# mcu.net
KiCad netlist of a schematic drawn in Altium Designer
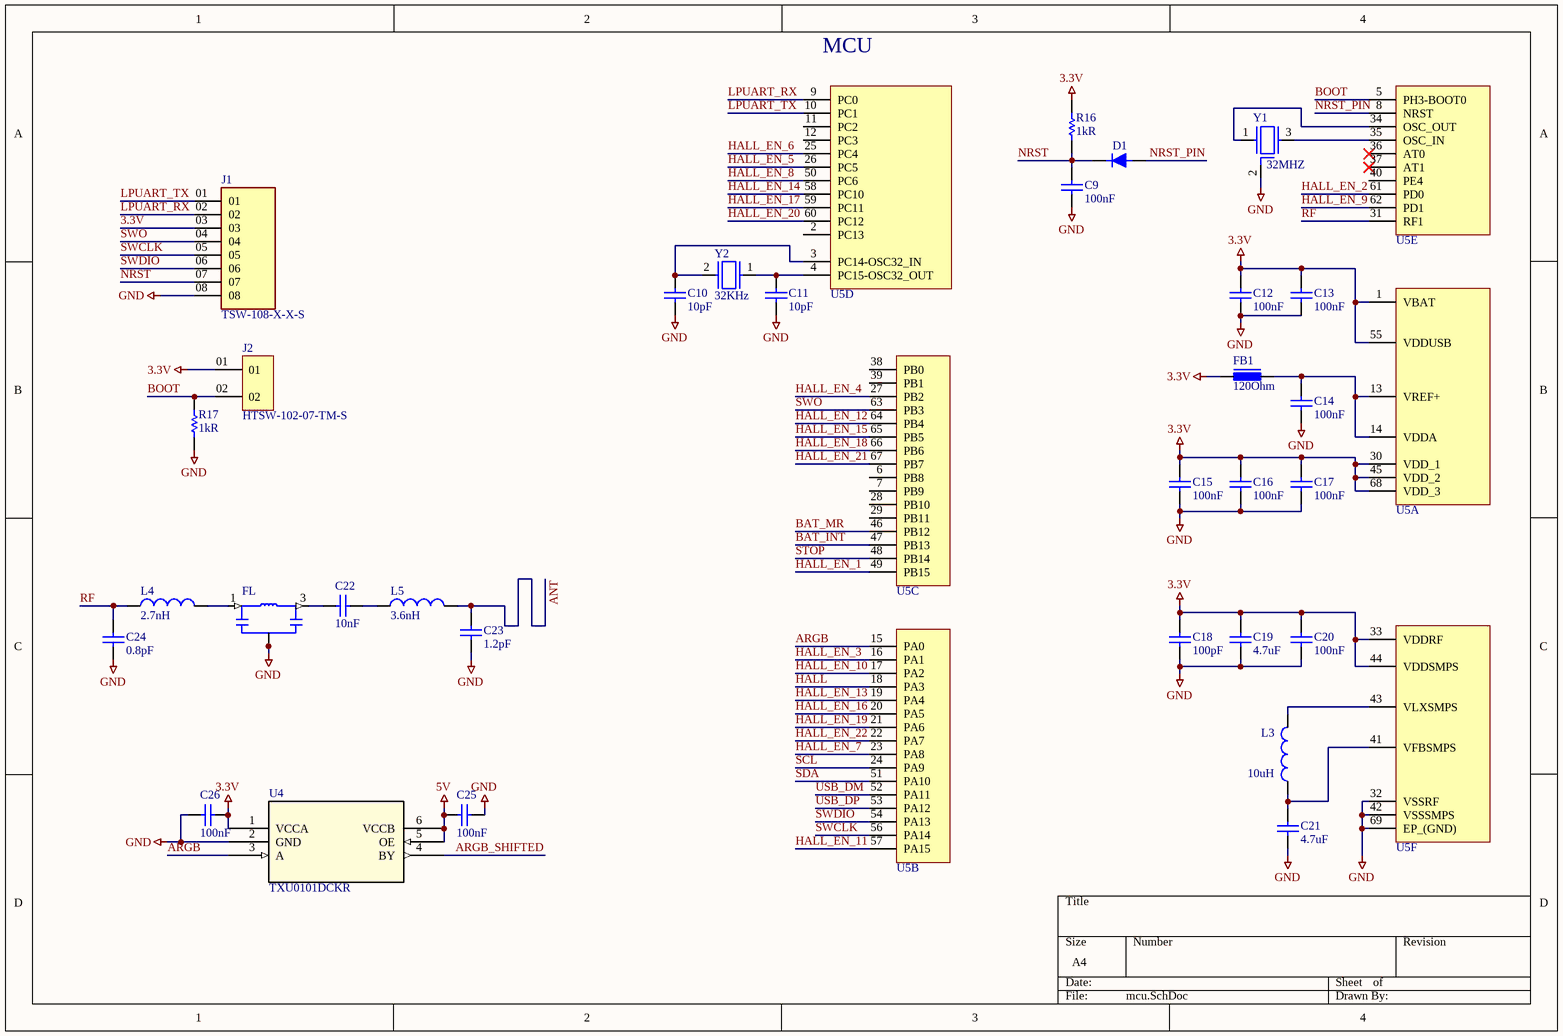
[diagram p0: mcu.SchDoc]

(export (version "E")
  (design (tool "Eeschema 10.0.6"))
  (components
    (comp (ref "C9")
      (value "100nF")
      (footprint "CAP_0402")
      (fields (field (name "MF") "Murata") (field (name "MP") "GRM022R60J222KE19L"))
      (libsource (lib "CAP_SMD") (part "Cap_100nF_0402"))
    )
    (comp (ref "C10")
      (value "10pF")
      (footprint "CAP_0402")
      (fields (field (name "MF") "Murata") (field (name "MP") "GRM022R60J222KE19L"))
      (libsource (lib "CAP_SMD") (part "Cap_10pF_0402"))
    )
    (comp (ref "C11")
      (value "10pF")
      (footprint "CAP_0402")
      (fields (field (name "MF") "Murata") (field (name "MP") "GRM022R60J222KE19L"))
      (libsource (lib "CAP_SMD") (part "Cap_10pF_0402"))
    )
    (comp (ref "C12")
      (value "100nF")
      (footprint "CAP_0402")
      (fields (field (name "MF") "Murata") (field (name "MP") "GRM022R60J222KE19L"))
      (libsource (lib "CAP_SMD") (part "Cap_100nF_0402"))
    )
    (comp (ref "C13")
      (value "100nF")
      (footprint "CAP_0402")
      (fields (field (name "MF") "Murata") (field (name "MP") "GRM022R60J222KE19L"))
      (libsource (lib "CAP_SMD") (part "Cap_100nF_0402"))
    )
    (comp (ref "C14")
      (value "100nF")
      (footprint "CAP_0402")
      (fields (field (name "MF") "Murata") (field (name "MP") "GRM022R60J222KE19L"))
      (libsource (lib "CAP_SMD") (part "Cap_100nF_0402"))
    )
    (comp (ref "C15")
      (value "100nF")
      (footprint "CAP_0402")
      (fields (field (name "MF") "Murata") (field (name "MP") "GRM022R60J222KE19L"))
      (libsource (lib "CAP_SMD") (part "Cap_100nF_0402"))
    )
    (comp (ref "C16")
      (value "100nF")
      (footprint "CAP_0402")
      (fields (field (name "MF") "Murata") (field (name "MP") "GRM022R60J222KE19L"))
      (libsource (lib "CAP_SMD") (part "Cap_100nF_0402"))
    )
    (comp (ref "C17")
      (value "100nF")
      (footprint "CAP_0402")
      (fields (field (name "MF") "Murata") (field (name "MP") "GRM022R60J222KE19L"))
      (libsource (lib "CAP_SMD") (part "Cap_100nF_0402"))
    )
    (comp (ref "C18")
      (value "100pF")
      (footprint "CAP_0402")
      (fields (field (name "MF") "Murata") (field (name "MP") "GRM022R60J222KE19L"))
      (libsource (lib "CAP_SMD") (part "Cap_100pF_0402"))
    )
    (comp (ref "C19")
      (value "4.7uF")
      (footprint "CAP_0402")
      (fields (field (name "MF") "Murata") (field (name "MP") "GRM022R60J222KE19L"))
      (libsource (lib "CAP_SMD") (part "Cap_4.7uF_0402"))
    )
    (comp (ref "C20")
      (value "100nF")
      (footprint "CAP_0402")
      (fields (field (name "MF") "Murata") (field (name "MP") "GRM022R60J222KE19L"))
      (libsource (lib "CAP_SMD") (part "Cap_100nF_0402"))
    )
    (comp (ref "C21")
      (value "4.7uF")
      (footprint "CAP_0402")
      (fields (field (name "MF") "Murata") (field (name "MP") "GRM022R60J222KE19L"))
      (libsource (lib "CAP_SMD") (part "Cap_4.7uF_0402"))
    )
    (comp (ref "C22")
      (value "10nF")
      (footprint "CAP_0402")
      (fields (field (name "MF") "Murata") (field (name "MP") "GRM022R60J222KE19L"))
      (libsource (lib "CAP_SMD") (part "Cap_10nF_0402"))
    )
    (comp (ref "C23")
      (value "1.2pF")
      (footprint "CAP_0402")
      (fields (field (name "MF") "Murata") (field (name "MP") "GRM022R60J222KE19L"))
      (libsource (lib "CAP_SMD") (part "Cap_1.2pF_0402"))
    )
    (comp (ref "C24")
      (value "0.8pF")
      (footprint "CAP_0402")
      (fields (field (name "MF") "Murata") (field (name "MP") "GRM022R60J222KE19L"))
      (libsource (lib "CAP_SMD") (part "Cap_0.8pF_0402"))
    )
    (comp (ref "C25")
      (value "100nF")
      (footprint "CAP_0402")
      (fields (field (name "MF") "Murata") (field (name "MP") "GRM022R60J222KE19L"))
      (libsource (lib "CAP_SMD") (part "Cap_100nF_0402"))
    )
    (comp (ref "C26")
      (value "100nF")
      (footprint "CAP_0402")
      (fields (field (name "MF") "Murata") (field (name "MP") "GRM022R60J222KE19L"))
      (libsource (lib "CAP_SMD") (part "Cap_100nF_0402"))
    )
    (comp (ref "D1")
      (value "0.3A")
      (footprint "SODFL1608X70N")
      (description "BAT54KFILM, Schottky Diode,  0.3A max, 40V 5ns, 2-Pin, SOD-523")
      (fields
        (field (name "MOUSER PART NUMBER") "511-BAT54KFILM")
        (field (name "MANUFACTURER_PART_NUMBER") "BAT54KFILM")
      )
      (libsource (lib "CHOCO_KEYBOARD") (part "BAT54KFILM"))
    )
    (comp (ref "FB1")
      (value "120Ohm")
      (footprint "BEADC1005X50N")
      (description "Ferrite Bead")
      (fields (field (name "MF") "Tai Tech") (field (name "MP") "FCM1608KF-601T05"))
      (libsource (lib "CHOCO_KEYBOARD") (part "MMZ1005S121CTD25"))
    )
    (comp (ref "FL")
      (value "LFB182G45CGFD436")
      (footprint "FIL_LFB182G45CGFD436")
      (description "RF Filter Band Pass 2450MHz 2400MHz to 2500MHz 2.8dB 50Ohm SMD 6Pin 0603")
      (fields (field (name "MF") "Murata"))
      (libsource (lib "LFB182G45CGFD436") (part "LFB182G45CGFD436"))
    )
    (comp (ref "J1")
      (value "TSW-108-X-X-S")
      (footprint "SAMTEC_TSW-108-X-X-S")
      (description "Connector Header Through Hole 8 position 0.100 (2.54mm)")
      (fields (field (name "MF") "Samtec") (field (name "MP") "TSW-108-23-L-S"))
      (libsource (lib "TSW-108-X-X-S") (part "TSW-108-X-X-S"))
    )
    (comp (ref "J2")
      (value "HTSW-102-07-TM-S")
      (footprint "SAMTEC_HTSW-102-07-TM-S")
      (fields (field (name "MP") "HTSW10207TMS") (field (name "MF") "Samtec"))
      (libsource (lib "CHOCO_KEYBOARD") (part "HTSW-102-07-TM-S"))
    )
    (comp (ref "L3")
      (value "10uH")
      (footprint "INDC1106X70N")
      (description "Inductor with Inductance: 10uH Tol. +/-20%, Package: 0402 (1005)")
      (fields (field (name "MP") "LQW15DN100M00D") (field (name "MF") "Murata Electronics North America"))
      (libsource (lib "LQW15DN100M00D") (part "LQW15DN100M00D"))
    )
    (comp (ref "L4")
      (value "2.7nH")
      (footprint "INDC1005X55N")
      (description "Inductor with Inductance: 3.6nH Tol. +/-0.3nH, Package: 0402 _1005_")
      (fields (field (name "MP") "LQG15HS3N6S02D") (field (name "MF") "Murata"))
      (libsource (lib "LQG15HS3N6S02D") (part "LQG15HS3N6S02D"))
    )
    (comp (ref "L5")
      (value "3.6nH")
      (footprint "INDC1005X55N")
      (description "Inductor with Inductance: 3.6nH Tol. +/-0.3nH, Package: 0402 _1005_")
      (fields (field (name "MP") "LQG15HS3N6S02D") (field (name "MF") "Murata"))
      (libsource (lib "LQG15HS3N6S02D") (part "LQG15HS3N6S02D"))
    )
    (comp (ref "R16") (value "1kR") (footprint "RES_0402") (libsource (lib "RES_SMD") (part "Res_1kR_0402")))
    (comp (ref "R17") (value "1kR") (footprint "RES_0402") (libsource (lib "RES_SMD") (part "Res_1kR_0402")))
    (comp (ref "U4")
      (value "TXU0101DCKR")
      (footprint "TXU0101DCKR")
      (libsource (lib "CHOCO_KEYBOARD") (part "TXU0101DCKR"))
    )
    (comp (ref "U5")
      (value "STM32WB55RGV6")
      (footprint "QFN40P800X800X100-69L-D")
      (libsource (lib "CHOCO_KEYBOARD") (part "STM32WB55RGV6"))
    )
    (comp (ref "Y1")
      (value "32MHZ")
      (footprint "SamacSys:NX2016SA32MEXS00ACS06465")
      (description "Crystal or Oscillator")
      (fields
        (field (name "MANUFACTURER_PART_NUMBER") "NX2016SA-26MHZ-EXS00A-CS06025")
        (field (name "MOUSER PART NUMBER") "344-NX2016SA26S06025")
      )
      (libsource (lib "CHOCO_KEYBOARD") (part "NX2016SA-32MHZ"))
    )
    (comp (ref "Y2")
      (value "32KHz")
      (footprint "SamacSys:NX2012SA32768KSTDMUB1")
      (description "Crystal or Oscillator")
      (fields
        (field (name "MANUFACTURER_PART_NUMBER") "NX2012SA-32.768K-STD-MUB-1")
        (field (name "MOUSER PART NUMBER") "344-NX2012SA32768K1")
      )
      (libsource (lib "CHOCO_KEYBOARD") (part "NX2012SA-32.768K"))
    )
  )
  (nets
    (net (code "1") (name "/ANT") (class "Default")
      (node (ref "C23") (pin "1") (pinfunction "1_1") (pintype "passive"))
      (node (ref "L5") (pin "2") (pinfunction "2_2") (pintype "passive"))
    )
    (net (code "2") (name "/ARGB") (class "Default")
      (node (ref "U4") (pin "3") (pinfunction "A_3") (pintype "input"))
      (node (ref "U5") (pin "15") (pinfunction "PA0_15") (pintype "passive"))
    )
    (net (code "3") (name "/ARGB_SHIFTED") (class "Default")
      (node (ref "U4") (pin "4") (pinfunction "BY_4") (pintype "output"))
    )
    (net (code "4") (name "/BAT_INT") (class "Default")
      (node (ref "U5") (pin "47") (pinfunction "PB13_47") (pintype "passive"))
    )
    (net (code "5") (name "/BAT_MR") (class "Default")
      (node (ref "U5") (pin "46") (pinfunction "PB12_46") (pintype "passive"))
    )
    (net (code "6") (name "/BOOT") (class "Default")
      (node (ref "J2") (pin "02") (pinfunction "02_02") (pintype "passive"))
      (node (ref "R17") (pin "2") (pinfunction "2_2") (pintype "passive"))
      (node (ref "U5") (pin "5") (pinfunction "PH3-BOOT0_5") (pintype "passive"))
    )
    (net (code "7") (name "/HALL") (class "Default")
      (node (ref "U5") (pin "18") (pinfunction "PA3_18") (pintype "passive"))
    )
    (net (code "8") (name "/HALL_EN_1") (class "Default")
      (node (ref "U5") (pin "49") (pinfunction "PB15_49") (pintype "passive"))
    )
    (net (code "9") (name "/HALL_EN_2") (class "Default")
      (node (ref "U5") (pin "61") (pinfunction "PD0_61") (pintype "passive"))
    )
    (net (code "10") (name "/HALL_EN_3") (class "Default")
      (node (ref "U5") (pin "16") (pinfunction "PA1_16") (pintype "passive"))
    )
    (net (code "11") (name "/HALL_EN_4") (class "Default")
      (node (ref "U5") (pin "27") (pinfunction "PB2_27") (pintype "passive"))
    )
    (net (code "12") (name "/HALL_EN_5") (class "Default")
      (node (ref "U5") (pin "26") (pinfunction "PC5_26") (pintype "passive"))
    )
    (net (code "13") (name "/HALL_EN_6") (class "Default")
      (node (ref "U5") (pin "25") (pinfunction "PC4_25") (pintype "passive"))
    )
    (net (code "14") (name "/HALL_EN_7") (class "Default")
      (node (ref "U5") (pin "23") (pinfunction "PA8_23") (pintype "passive"))
    )
    (net (code "15") (name "/HALL_EN_8") (class "Default")
      (node (ref "U5") (pin "50") (pinfunction "PC6_50") (pintype "passive"))
    )
    (net (code "16") (name "/HALL_EN_9") (class "Default")
      (node (ref "U5") (pin "62") (pinfunction "PD1_62") (pintype "passive"))
    )
    (net (code "17") (name "/HALL_EN_10") (class "Default")
      (node (ref "U5") (pin "17") (pinfunction "PA2_17") (pintype "passive"))
    )
    (net (code "18") (name "/HALL_EN_11") (class "Default")
      (node (ref "U5") (pin "57") (pinfunction "PA15_57") (pintype "passive"))
    )
    (net (code "19") (name "/HALL_EN_12") (class "Default")
      (node (ref "U5") (pin "64") (pinfunction "PB4_64") (pintype "passive"))
    )
    (net (code "20") (name "/HALL_EN_13") (class "Default")
      (node (ref "U5") (pin "19") (pinfunction "PA4_19") (pintype "passive"))
    )
    (net (code "21") (name "/HALL_EN_14") (class "Default")
      (node (ref "U5") (pin "58") (pinfunction "PC10_58") (pintype "passive"))
    )
    (net (code "22") (name "/HALL_EN_15") (class "Default")
      (node (ref "U5") (pin "65") (pinfunction "PB5_65") (pintype "passive"))
    )
    (net (code "23") (name "/HALL_EN_16") (class "Default")
      (node (ref "U5") (pin "20") (pinfunction "PA5_20") (pintype "passive"))
    )
    (net (code "24") (name "/HALL_EN_17") (class "Default")
      (node (ref "U5") (pin "59") (pinfunction "PC11_59") (pintype "passive"))
    )
    (net (code "25") (name "/HALL_EN_18") (class "Default")
      (node (ref "U5") (pin "66") (pinfunction "PB6_66") (pintype "passive"))
    )
    (net (code "26") (name "/HALL_EN_19") (class "Default")
      (node (ref "U5") (pin "21") (pinfunction "PA6_21") (pintype "passive"))
    )
    (net (code "27") (name "/HALL_EN_20") (class "Default")
      (node (ref "U5") (pin "60") (pinfunction "PC12_60") (pintype "passive"))
    )
    (net (code "28") (name "/HALL_EN_21") (class "Default")
      (node (ref "U5") (pin "67") (pinfunction "PB7_67") (pintype "passive"))
    )
    (net (code "29") (name "/HALL_EN_22") (class "Default")
      (node (ref "U5") (pin "22") (pinfunction "PA7_22") (pintype "passive"))
    )
    (net (code "30") (name "/LPUART_RX") (class "Default")
      (node (ref "J1") (pin "02") (pinfunction "02_02") (pintype "passive"))
      (node (ref "U5") (pin "9") (pinfunction "PC0_9") (pintype "passive"))
    )
    (net (code "31") (name "/LPUART_TX") (class "Default")
      (node (ref "J1") (pin "01") (pinfunction "01_01") (pintype "passive"))
      (node (ref "U5") (pin "10") (pinfunction "PC1_10") (pintype "passive"))
    )
    (net (code "32") (name "/NRST") (class "Default")
      (node (ref "C9") (pin "1") (pinfunction "1_1") (pintype "passive"))
      (node (ref "D1") (pin "1") (pinfunction "K_1") (pintype "passive"))
      (node (ref "J1") (pin "07") (pinfunction "07_07") (pintype "passive"))
      (node (ref "R16") (pin "1") (pinfunction "1_1") (pintype "passive"))
    )
    (net (code "33") (name "/NRST_PIN") (class "Default")
      (node (ref "D1") (pin "2") (pinfunction "A_2") (pintype "passive"))
      (node (ref "U5") (pin "8") (pinfunction "NRST_8") (pintype "passive"))
    )
    (net (code "34") (name "/RF") (class "Default")
      (node (ref "C24") (pin "2") (pinfunction "2_2") (pintype "passive"))
      (node (ref "L4") (pin "1") (pinfunction "1_1") (pintype "passive"))
      (node (ref "U5") (pin "31") (pinfunction "RF1_31") (pintype "passive"))
    )
    (net (code "35") (name "/SCL") (class "Default")
      (node (ref "U5") (pin "24") (pinfunction "PA9_24") (pintype "passive"))
    )
    (net (code "36") (name "/SDA") (class "Default")
      (node (ref "U5") (pin "51") (pinfunction "PA10_51") (pintype "passive"))
    )
    (net (code "37") (name "/STOP") (class "Default")
      (node (ref "U5") (pin "48") (pinfunction "PB14_48") (pintype "passive"))
    )
    (net (code "38") (name "/SWCLK") (class "Default")
      (node (ref "J1") (pin "05") (pinfunction "05_05") (pintype "passive"))
      (node (ref "U5") (pin "56") (pinfunction "PA14_56") (pintype "passive"))
    )
    (net (code "39") (name "/SWDIO") (class "Default")
      (node (ref "J1") (pin "06") (pinfunction "06_06") (pintype "passive"))
      (node (ref "U5") (pin "54") (pinfunction "PA13_54") (pintype "passive"))
    )
    (net (code "40") (name "/SWO") (class "Default")
      (node (ref "J1") (pin "04") (pinfunction "04_04") (pintype "passive"))
      (node (ref "U5") (pin "63") (pinfunction "PB3_63") (pintype "passive"))
    )
    (net (code "41") (name "/USB_DM") (class "Default")
      (node (ref "U5") (pin "52") (pinfunction "PA11_52") (pintype "passive"))
    )
    (net (code "42") (name "/USB_DP") (class "Default")
      (node (ref "U5") (pin "53") (pinfunction "PA12_53") (pintype "passive"))
    )
    (net (code "43") (name "3.3V") (class "Default")
      (node (ref "C12") (pin "2") (pinfunction "2_2") (pintype "passive"))
      (node (ref "C13") (pin "2") (pinfunction "2_2") (pintype "passive"))
      (node (ref "C15") (pin "2") (pinfunction "2_2") (pintype "passive"))
      (node (ref "C16") (pin "2") (pinfunction "2_2") (pintype "passive"))
      (node (ref "C17") (pin "2") (pinfunction "2_2") (pintype "passive"))
      (node (ref "C18") (pin "2") (pinfunction "2_2") (pintype "passive"))
      (node (ref "C19") (pin "2") (pinfunction "2_2") (pintype "passive"))
      (node (ref "C20") (pin "2") (pinfunction "2_2") (pintype "passive"))
      (node (ref "C26") (pin "1") (pinfunction "1_1") (pintype "passive"))
      (node (ref "FB1") (pin "1") (pinfunction "1_1") (pintype "passive"))
      (node (ref "J1") (pin "03") (pinfunction "03_03") (pintype "passive"))
      (node (ref "J2") (pin "01") (pinfunction "01_01") (pintype "passive"))
      (node (ref "R16") (pin "2") (pinfunction "2_2") (pintype "passive"))
      (node (ref "U4") (pin "1") (pinfunction "VCCA_1") (pintype "power_in"))
      (node (ref "U5") (pin "1") (pinfunction "VBAT_1") (pintype "passive"))
      (node (ref "U5") (pin "30") (pinfunction "VDD_1_30") (pintype "passive"))
      (node (ref "U5") (pin "33") (pinfunction "VDDRF_33") (pintype "passive"))
      (node (ref "U5") (pin "44") (pinfunction "VDDSMPS_44") (pintype "passive"))
      (node (ref "U5") (pin "45") (pinfunction "VDD_2_45") (pintype "passive"))
      (node (ref "U5") (pin "55") (pinfunction "VDDUSB_55") (pintype "passive"))
      (node (ref "U5") (pin "68") (pinfunction "VDD_3_68") (pintype "passive"))
    )
    (net (code "44") (name "5V") (class "Default")
      (node (ref "C25") (pin "2") (pinfunction "2_2") (pintype "passive"))
      (node (ref "U4") (pin "5") (pinfunction "OE_5") (pintype "input"))
      (node (ref "U4") (pin "6") (pinfunction "VCCB_6") (pintype "power_in"))
    )
    (net (code "45") (name "GND") (class "Default")
      (node (ref "C10") (pin "1") (pinfunction "1_1") (pintype "passive"))
      (node (ref "C11") (pin "1") (pinfunction "1_1") (pintype "passive"))
      (node (ref "C12") (pin "1") (pinfunction "1_1") (pintype "passive"))
      (node (ref "C13") (pin "1") (pinfunction "1_1") (pintype "passive"))
      (node (ref "C14") (pin "1") (pinfunction "1_1") (pintype "passive"))
      (node (ref "C15") (pin "1") (pinfunction "1_1") (pintype "passive"))
      (node (ref "C16") (pin "1") (pinfunction "1_1") (pintype "passive"))
      (node (ref "C17") (pin "1") (pinfunction "1_1") (pintype "passive"))
      (node (ref "C18") (pin "1") (pinfunction "1_1") (pintype "passive"))
      (node (ref "C19") (pin "1") (pinfunction "1_1") (pintype "passive"))
      (node (ref "C20") (pin "1") (pinfunction "1_1") (pintype "passive"))
      (node (ref "C21") (pin "1") (pinfunction "1_1") (pintype "passive"))
      (node (ref "C23") (pin "2") (pinfunction "2_2") (pintype "passive"))
      (node (ref "C24") (pin "1") (pinfunction "1_1") (pintype "passive"))
      (node (ref "C25") (pin "1") (pinfunction "1_1") (pintype "passive"))
      (node (ref "C26") (pin "2") (pinfunction "2_2") (pintype "passive"))
      (node (ref "C9") (pin "2") (pinfunction "2_2") (pintype "passive"))
      (node (ref "FL") (pin "2") (pinfunction "GND_2") (pintype "power_in"))
      (node (ref "FL") (pin "2_1") (pinfunction "GND_2_1") (pintype "power_in"))
      (node (ref "J1") (pin "08") (pinfunction "08_08") (pintype "passive"))
      (node (ref "R17") (pin "1") (pinfunction "1_1") (pintype "passive"))
      (node (ref "U4") (pin "2") (pinfunction "GND_2") (pintype "power_in"))
      (node (ref "U5") (pin "32") (pinfunction "VSSRF_32") (pintype "passive"))
      (node (ref "U5") (pin "42") (pinfunction "VSSSMPS_42") (pintype "passive"))
      (node (ref "U5") (pin "69") (pinfunction "EP_(GND)_69") (pintype "passive"))
      (node (ref "Y1") (pin "2") (pinfunction "GND_2") (pintype "passive"))
    )
    (net (code "46") (name "Net-(C22-Pad2)") (class "Default")
      (node (ref "C22") (pin "2") (pinfunction "2_2") (pintype "passive"))
      (node (ref "L5") (pin "1") (pinfunction "1_1") (pintype "passive"))
    )
    (net (code "47") (name "Net-(FL-IN)") (class "Default")
      (node (ref "FL") (pin "1") (pinfunction "IN_1") (pintype "input"))
      (node (ref "L4") (pin "2") (pinfunction "2_2") (pintype "passive"))
    )
    (net (code "48") (name "Net-(FL-OUT)") (class "Default")
      (node (ref "C22") (pin "1") (pinfunction "1_1") (pintype "passive"))
      (node (ref "FL") (pin "3") (pinfunction "OUT_3") (pintype "output"))
    )
    (net (code "49") (name "Net-(U5A-VDDA)") (class "Default")
      (node (ref "C14") (pin "2") (pinfunction "2_2") (pintype "passive"))
      (node (ref "FB1") (pin "2") (pinfunction "2_2") (pintype "passive"))
      (node (ref "U5") (pin "13") (pinfunction "VREF+_13") (pintype "passive"))
      (node (ref "U5") (pin "14") (pinfunction "VDDA_14") (pintype "passive"))
    )
    (net (code "50") (name "Net-(U5D-PC14-OSC32_IN)") (class "Default")
      (node (ref "C10") (pin "2") (pinfunction "2_2") (pintype "passive"))
      (node (ref "U5") (pin "3") (pinfunction "PC14-OSC32_IN_3") (pintype "passive"))
      (node (ref "Y2") (pin "2") (pinfunction "CRYSTAL_2_2") (pintype "passive"))
    )
    (net (code "51") (name "Net-(U5D-PC15-OSC32_OUT)") (class "Default")
      (node (ref "C11") (pin "2") (pinfunction "2_2") (pintype "passive"))
      (node (ref "U5") (pin "4") (pinfunction "PC15-OSC32_OUT_4") (pintype "passive"))
      (node (ref "Y2") (pin "1") (pinfunction "CRYSTAL_1_1") (pintype "passive"))
    )
    (net (code "52") (name "Net-(U5E-OSC_IN)") (class "Default")
      (node (ref "U5") (pin "35") (pinfunction "OSC_IN_35") (pintype "passive"))
      (node (ref "Y1") (pin "3") (pinfunction "CRYSTAL_2_3") (pintype "passive"))
    )
    (net (code "53") (name "Net-(U5E-OSC_OUT)") (class "Default")
      (node (ref "U5") (pin "34") (pinfunction "OSC_OUT_34") (pintype "passive"))
      (node (ref "Y1") (pin "1") (pinfunction "CRYSTAL_1_1") (pintype "passive"))
    )
    (net (code "54") (name "Net-(U5F-VFBSMPS)") (class "Default")
      (node (ref "C21") (pin "2") (pinfunction "2_2") (pintype "passive"))
      (node (ref "L3") (pin "1") (pinfunction "1_1") (pintype "passive"))
      (node (ref "U5") (pin "41") (pinfunction "VFBSMPS_41") (pintype "passive"))
    )
    (net (code "55") (name "Net-(U5F-VLXSMPS)") (class "Default")
      (node (ref "L3") (pin "2") (pinfunction "2_2") (pintype "passive"))
      (node (ref "U5") (pin "43") (pinfunction "VLXSMPS_43") (pintype "passive"))
    )
    (net (code "56") (name "unconnected-(U5C-PB0-Pad38)") (class "Default")
      (node (ref "U5") (pin "38") (pinfunction "PB0_38") (pintype "passive"))
    )
    (net (code "57") (name "unconnected-(U5C-PB1-Pad39)") (class "Default")
      (node (ref "U5") (pin "39") (pinfunction "PB1_39") (pintype "passive"))
    )
    (net (code "58") (name "unconnected-(U5C-PB8-Pad6)") (class "Default")
      (node (ref "U5") (pin "6") (pinfunction "PB8_6") (pintype "passive"))
    )
    (net (code "59") (name "unconnected-(U5C-PB9-Pad7)") (class "Default")
      (node (ref "U5") (pin "7") (pinfunction "PB9_7") (pintype "passive"))
    )
    (net (code "60") (name "unconnected-(U5C-PB10-Pad28)") (class "Default")
      (node (ref "U5") (pin "28") (pinfunction "PB10_28") (pintype "passive"))
    )
    (net (code "61") (name "unconnected-(U5C-PB11-Pad29)") (class "Default")
      (node (ref "U5") (pin "29") (pinfunction "PB11_29") (pintype "passive"))
    )
    (net (code "62") (name "unconnected-(U5D-PC2-Pad11)") (class "Default")
      (node (ref "U5") (pin "11") (pinfunction "PC2_11") (pintype "passive"))
    )
    (net (code "63") (name "unconnected-(U5D-PC3-Pad12)") (class "Default")
      (node (ref "U5") (pin "12") (pinfunction "PC3_12") (pintype "passive"))
    )
    (net (code "64") (name "unconnected-(U5D-PC13-Pad2)") (class "Default")
      (node (ref "U5") (pin "2") (pinfunction "PC13_2") (pintype "passive"))
    )
    (net (code "65") (name "unconnected-(U5E-AT0-Pad36)") (class "Default")
      (node (ref "U5") (pin "36") (pinfunction "AT0_36") (pintype "passive+no_connect"))
    )
    (net (code "66") (name "unconnected-(U5E-AT1-Pad37)") (class "Default")
      (node (ref "U5") (pin "37") (pinfunction "AT1_37") (pintype "passive+no_connect"))
    )
    (net (code "67") (name "unconnected-(U5E-PE4-Pad40)") (class "Default")
      (node (ref "U5") (pin "40") (pinfunction "PE4_40") (pintype "passive"))
    )
  )
)
